# main.net
KiCad netlist of a schematic drawn in EAGLE
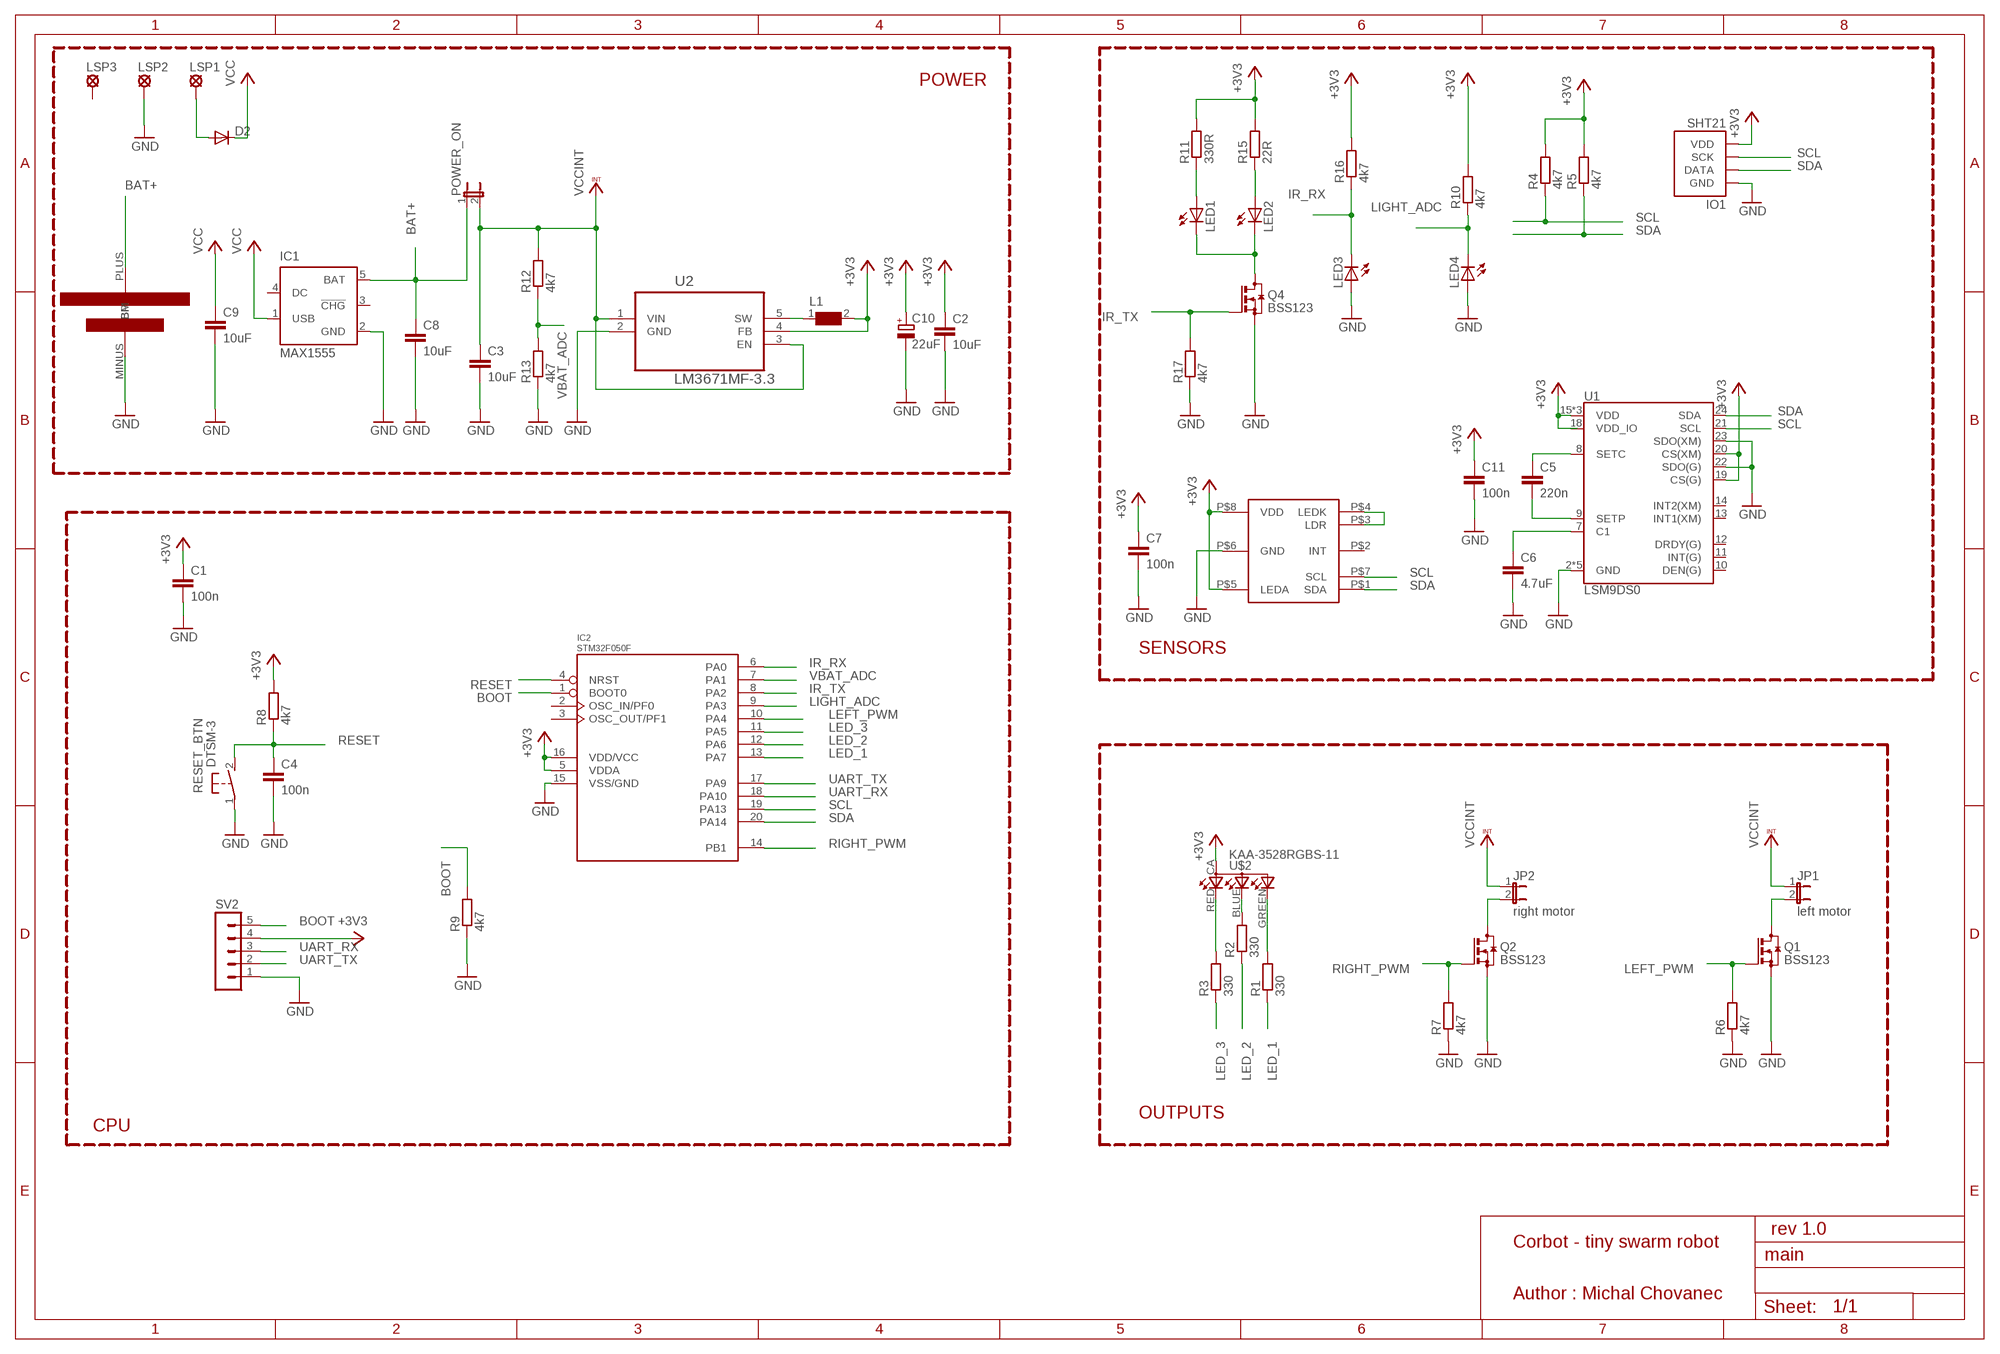
[diagram p0: schematic, sheet 1]

(export (version "E")
  (design (tool "Eeschema 10.0.6"))
  (components
    (comp (ref "C1")
      (value "100n")
      (footprint "eagle-import:C0805")
      (libsource (lib "eagle-import") (part "C-EUC0805"))
    )
    (comp (ref "C2")
      (value "10uF")
      (footprint "eagle-import:C0805")
      (libsource (lib "eagle-import") (part "C-EUC0805"))
    )
    (comp (ref "C3")
      (value "10uF")
      (footprint "eagle-import:C0805")
      (libsource (lib "eagle-import") (part "C-EUC0805"))
    )
    (comp (ref "C4")
      (value "100n")
      (footprint "eagle-import:C0805")
      (libsource (lib "eagle-import") (part "C-EUC0805"))
    )
    (comp (ref "C5")
      (value "220n")
      (footprint "eagle-import:C0805")
      (libsource (lib "eagle-import") (part "C-EUC0805"))
    )
    (comp (ref "C6")
      (value "4.7uF")
      (footprint "eagle-import:C0805")
      (libsource (lib "eagle-import") (part "C-EUC0805"))
    )
    (comp (ref "C7")
      (value "100n")
      (footprint "eagle-import:C0805")
      (libsource (lib "eagle-import") (part "C-EUC0805"))
    )
    (comp (ref "C8")
      (value "10uF")
      (footprint "eagle-import:C0805")
      (libsource (lib "eagle-import") (part "C-EUC0805"))
    )
    (comp (ref "C9")
      (value "10uF")
      (footprint "eagle-import:C0805")
      (libsource (lib "eagle-import") (part "C-EUC0805"))
    )
    (comp (ref "C10")
      (value "22uF")
      (footprint "eagle-import:153CLV-0505")
      (libsource (lib "eagle-import") (part "CPOL-EU153CLV-0505"))
    )
    (comp (ref "C11")
      (value "100n")
      (footprint "eagle-import:C0805")
      (libsource (lib "eagle-import") (part "C-EUC0805"))
    )
    (comp (ref "D2")
      (value "DIODE-DO-214AC")
      (footprint "eagle-import:DO-214AC")
      (libsource (lib "eagle-import") (part "DIODE-DO-214AC"))
    )
    (comp (ref "IC1")
      (value "MAX1555")
      (footprint "eagle-import:SOT23-5L")
      (fields (field (name "MF") "MAXIM") (field (name "MPN") "MAX1555EZK+T"))
      (libsource (lib "eagle-import") (part "MAX1555"))
    )
    (comp (ref "IC2")
      (value "STM32F050F")
      (footprint "eagle-import:TSSOP20")
      (libsource (lib "eagle-import") (part "STM32F050F"))
    )
    (comp (ref "IO1")
      (value "SHT21")
      (footprint "eagle-import:SHT2X")
      (libsource (lib "eagle-import") (part "SHT21"))
    )
    (comp (ref "JP1")
      (value "left motor")
      (footprint "eagle-import:JP1")
      (libsource (lib "eagle-import") (part "JP1E"))
    )
    (comp (ref "JP2")
      (value "right motor")
      (footprint "eagle-import:JP1")
      (libsource (lib "eagle-import") (part "JP1E"))
    )
    (comp (ref "L1")
      (value "WE-LQ-744032002_M")
      (footprint "eagle-import:WE-LQ_M")
      (fields (field (name "MPN") "744032002 "))
      (libsource (lib "eagle-import") (part "WE-LQ_M-744032002"))
    )
    (comp (ref "LED1")
      (value "LEDCHIPLED_1206")
      (footprint "eagle-import:CHIPLED_1206")
      (libsource (lib "eagle-import") (part "LEDCHIPLED_1206"))
    )
    (comp (ref "LED2")
      (value "LEDCHIPLED_1206")
      (footprint "eagle-import:CHIPLED_1206")
      (libsource (lib "eagle-import") (part "LEDCHIPLED_1206"))
    )
    (comp (ref "LED3")
      (value "LEDCHIPLED_1206")
      (footprint "eagle-import:CHIPLED_1206")
      (libsource (lib "eagle-import") (part "LEDCHIPLED_1206"))
    )
    (comp (ref "LED4")
      (value "LEDCHIPLED_1206")
      (footprint "eagle-import:CHIPLED_1206")
      (libsource (lib "eagle-import") (part "LEDCHIPLED_1206"))
    )
    (comp (ref "LSP1")
      (value "LSP13")
      (footprint "eagle-import:LSP13")
      (libsource (lib "eagle-import") (part "LSP13"))
    )
    (comp (ref "LSP2")
      (value "LSP13")
      (footprint "eagle-import:LSP13")
      (libsource (lib "eagle-import") (part "LSP13"))
    )
    (comp (ref "LSP3")
      (value "LSP13")
      (footprint "eagle-import:LSP13")
      (libsource (lib "eagle-import") (part "LSP13"))
    )
    (comp (ref "POWER_ON")
      (value "JP1E")
      (footprint "eagle-import:JP1")
      (libsource (lib "eagle-import") (part "JP1E"))
    )
    (comp (ref "Q1")
      (value "BSS123")
      (footprint "eagle-import:SOT23")
      (libsource (lib "eagle-import") (part "BSS123"))
    )
    (comp (ref "Q2")
      (value "BSS123")
      (footprint "eagle-import:SOT23")
      (libsource (lib "eagle-import") (part "BSS123"))
    )
    (comp (ref "Q4")
      (value "BSS123")
      (footprint "eagle-import:SOT23")
      (libsource (lib "eagle-import") (part "BSS123"))
    )
    (comp (ref "R1")
      (value "330")
      (footprint "eagle-import:M0805")
      (libsource (lib "eagle-import") (part "R-EU_M0805"))
    )
    (comp (ref "R2")
      (value "330")
      (footprint "eagle-import:M0805")
      (libsource (lib "eagle-import") (part "R-EU_M0805"))
    )
    (comp (ref "R3")
      (value "330")
      (footprint "eagle-import:M0805")
      (libsource (lib "eagle-import") (part "R-EU_M0805"))
    )
    (comp (ref "R4")
      (value "4k7")
      (footprint "eagle-import:M0805")
      (libsource (lib "eagle-import") (part "R-EU_M0805"))
    )
    (comp (ref "R5")
      (value "4k7")
      (footprint "eagle-import:M0805")
      (libsource (lib "eagle-import") (part "R-EU_M0805"))
    )
    (comp (ref "R6")
      (value "4k7")
      (footprint "eagle-import:M0805")
      (libsource (lib "eagle-import") (part "R-EU_M0805"))
    )
    (comp (ref "R7")
      (value "4k7")
      (footprint "eagle-import:M0805")
      (libsource (lib "eagle-import") (part "R-EU_M0805"))
    )
    (comp (ref "R8")
      (value "4k7")
      (footprint "eagle-import:M0805")
      (libsource (lib "eagle-import") (part "R-EU_M0805"))
    )
    (comp (ref "R9")
      (value "4k7")
      (footprint "eagle-import:M0805")
      (libsource (lib "eagle-import") (part "R-EU_M0805"))
    )
    (comp (ref "R10")
      (value "4k7")
      (footprint "eagle-import:M0805")
      (libsource (lib "eagle-import") (part "R-EU_M0805"))
    )
    (comp (ref "R11")
      (value "330R")
      (footprint "eagle-import:M0805")
      (libsource (lib "eagle-import") (part "R-EU_M0805"))
    )
    (comp (ref "R12")
      (value "4k7")
      (footprint "eagle-import:M0805")
      (libsource (lib "eagle-import") (part "R-EU_M0805"))
    )
    (comp (ref "R13")
      (value "4k7")
      (footprint "eagle-import:M0805")
      (libsource (lib "eagle-import") (part "R-EU_M0805"))
    )
    (comp (ref "R15")
      (value "22R")
      (footprint "eagle-import:M0805")
      (libsource (lib "eagle-import") (part "R-EU_M0805"))
    )
    (comp (ref "R16")
      (value "4k7")
      (footprint "eagle-import:M0805")
      (libsource (lib "eagle-import") (part "R-EU_M0805"))
    )
    (comp (ref "R17")
      (value "4k7")
      (footprint "eagle-import:M0805")
      (libsource (lib "eagle-import") (part "R-EU_M0805"))
    )
    (comp (ref "RESET_BTN")
      (value "DTSM-3")
      (footprint "eagle-import:DTSM-3")
      (libsource (lib "eagle-import") (part "DTSM-3"))
    )
    (comp (ref "SV2")
      (value "MA05-1")
      (footprint "eagle-import:MA05-1")
      (libsource (lib "eagle-import") (part "MA05-1"))
    )
    (comp (ref "U$1")
      (value "SMTU_2450N")
      (footprint "eagle-import:SMTU_2450N")
      (libsource (lib "eagle-import") (part "SMTU_2450N"))
    )
    (comp (ref "U$2")
      (value "KAA-3528RGBS-11")
      (footprint "eagle-import:LED-RGB")
      (libsource (lib "eagle-import") (part "KAA-3528RGBS-11"))
    )
    (comp (ref "U$3")
      (value "APDS9950")
      (footprint "eagle-import:APDS9950")
      (libsource (lib "eagle-import") (part "APDS9950"))
    )
    (comp (ref "U1")
      (value "LSM9DS0")
      (footprint "eagle-import:LGA-24")
      (libsource (lib "eagle-import") (part "LSM9DS0"))
    )
    (comp (ref "U2")
      (value "LM3671MF-3.3")
      (footprint "eagle-import:SOT95P284X122-5N")
      (libsource (lib "eagle-import") (part "LM3671MF-3.3"))
    )
  )
  (nets
    (net (code "1") (name "+3V3") (class "Default")
      (node (ref "C1") (pin "1") (pinfunction "1_1") (pintype "passive"))
      (node (ref "C10") (pin "+") (pinfunction "+_+") (pintype "passive"))
      (node (ref "C11") (pin "1") (pinfunction "1_1") (pintype "passive"))
      (node (ref "C2") (pin "1") (pinfunction "1_1") (pintype "passive"))
      (node (ref "C7") (pin "1") (pinfunction "1_1") (pintype "passive"))
      (node (ref "IC2") (pin "16") (pinfunction "VDD/VCC_16") (pintype "power_in"))
      (node (ref "IC2") (pin "5") (pinfunction "VDDA_5") (pintype "power_in"))
      (node (ref "IO1") (pin "5") (pinfunction "VDD_5") (pintype "power_in"))
      (node (ref "L1") (pin "2") (pinfunction "2_2") (pintype "passive"))
      (node (ref "R10") (pin "2") (pinfunction "2_2") (pintype "passive"))
      (node (ref "R11") (pin "2") (pinfunction "2_2") (pintype "passive"))
      (node (ref "R15") (pin "2") (pinfunction "2_2") (pintype "passive"))
      (node (ref "R16") (pin "2") (pinfunction "2_2") (pintype "passive"))
      (node (ref "R4") (pin "2") (pinfunction "2_2") (pintype "passive"))
      (node (ref "R5") (pin "2") (pinfunction "2_2") (pintype "passive"))
      (node (ref "R8") (pin "2") (pinfunction "2_2") (pintype "passive"))
      (node (ref "SV2") (pin "4") (pinfunction "4_4") (pintype "passive"))
      (node (ref "U$2") (pin "CA") (pinfunction "A_CA") (pintype "passive"))
      (node (ref "U$3") (pin "P$5") (pinfunction "LEDA_P$5") (pintype "bidirectional"))
      (node (ref "U$3") (pin "P$8") (pinfunction "VDD_P$8") (pintype "bidirectional"))
      (node (ref "U1") (pin "15") (pinfunction "VDD_15") (pintype "bidirectional"))
      (node (ref "U1") (pin "16") (pinfunction "VDD_16") (pintype "bidirectional"))
      (node (ref "U1") (pin "17") (pinfunction "VDD_17") (pintype "bidirectional"))
      (node (ref "U1") (pin "19") (pinfunction "CS(G)_19") (pintype "bidirectional"))
      (node (ref "U1") (pin "20") (pinfunction "CS(XM)_20") (pintype "bidirectional"))
      (node (ref "U2") (pin "4") (pinfunction "FB_4") (pintype "passive"))
    )
    (net (code "2") (name "/BAT+") (class "Default")
      (node (ref "C8") (pin "1") (pinfunction "1_1") (pintype "passive"))
      (node (ref "IC1") (pin "5") (pinfunction "BAT_5") (pintype "passive"))
      (node (ref "POWER_ON") (pin "1") (pinfunction "1_1") (pintype "passive"))
      (node (ref "U$1") (pin "PLUS") (pinfunction "BP_PLUS") (pintype "bidirectional"))
    )
    (net (code "3") (name "/BOOT") (class "Default")
      (node (ref "IC2") (pin "1") (pinfunction "BOOT0_1") (pintype "bidirectional"))
      (node (ref "R9") (pin "2") (pinfunction "2_2") (pintype "passive"))
      (node (ref "SV2") (pin "5") (pinfunction "5_5") (pintype "passive"))
    )
    (net (code "4") (name "/IR_RX") (class "Default")
      (node (ref "IC2") (pin "6") (pinfunction "PA0_6") (pintype "bidirectional"))
      (node (ref "LED3") (pin "C") (pinfunction "C_C") (pintype "passive"))
      (node (ref "R16") (pin "1") (pinfunction "1_1") (pintype "passive"))
    )
    (net (code "5") (name "/IR_TX") (class "Default")
      (node (ref "IC2") (pin "8") (pinfunction "PA2_8") (pintype "bidirectional"))
      (node (ref "Q4") (pin "1") (pinfunction "G_1") (pintype "passive"))
      (node (ref "R17") (pin "2") (pinfunction "2_2") (pintype "passive"))
    )
    (net (code "6") (name "/LED_1") (class "Default")
      (node (ref "IC2") (pin "13") (pinfunction "PA7_13") (pintype "bidirectional"))
      (node (ref "R1") (pin "1") (pinfunction "1_1") (pintype "passive"))
    )
    (net (code "7") (name "/LED_2") (class "Default")
      (node (ref "IC2") (pin "12") (pinfunction "PA6_12") (pintype "bidirectional"))
      (node (ref "R2") (pin "1") (pinfunction "1_1") (pintype "passive"))
    )
    (net (code "8") (name "/LED_3") (class "Default")
      (node (ref "IC2") (pin "11") (pinfunction "PA5_11") (pintype "bidirectional"))
      (node (ref "R3") (pin "1") (pinfunction "1_1") (pintype "passive"))
    )
    (net (code "9") (name "/LEFT_PWM") (class "Default")
      (node (ref "IC2") (pin "10") (pinfunction "PA4_10") (pintype "bidirectional"))
      (node (ref "Q1") (pin "1") (pinfunction "G_1") (pintype "passive"))
      (node (ref "R6") (pin "2") (pinfunction "2_2") (pintype "passive"))
    )
    (net (code "10") (name "/LIGHT_ADC") (class "Default")
      (node (ref "IC2") (pin "9") (pinfunction "PA3_9") (pintype "bidirectional"))
      (node (ref "LED4") (pin "C") (pinfunction "C_C") (pintype "passive"))
      (node (ref "R10") (pin "1") (pinfunction "1_1") (pintype "passive"))
    )
    (net (code "11") (name "/RESET") (class "Default")
      (node (ref "C4") (pin "1") (pinfunction "1_1") (pintype "passive"))
      (node (ref "IC2") (pin "4") (pinfunction "NRST_4") (pintype "bidirectional"))
      (node (ref "R8") (pin "1") (pinfunction "1_1") (pintype "passive"))
      (node (ref "RESET_BTN") (pin "2") (pinfunction "2_2") (pintype "passive"))
    )
    (net (code "12") (name "/RIGHT_PWM") (class "Default")
      (node (ref "IC2") (pin "14") (pinfunction "PB1_14") (pintype "bidirectional"))
      (node (ref "Q2") (pin "1") (pinfunction "G_1") (pintype "passive"))
      (node (ref "R7") (pin "2") (pinfunction "2_2") (pintype "passive"))
    )
    (net (code "13") (name "/SCL") (class "Default")
      (node (ref "IC2") (pin "19") (pinfunction "PA13_19") (pintype "bidirectional"))
      (node (ref "IO1") (pin "4") (pinfunction "SCK_4") (pintype "input"))
      (node (ref "R4") (pin "1") (pinfunction "1_1") (pintype "passive"))
      (node (ref "U$3") (pin "P$7") (pinfunction "SCL_P$7") (pintype "bidirectional"))
      (node (ref "U1") (pin "21") (pinfunction "SCL_21") (pintype "bidirectional"))
    )
    (net (code "14") (name "/SDA") (class "Default")
      (node (ref "IC2") (pin "20") (pinfunction "PA14_20") (pintype "bidirectional"))
      (node (ref "IO1") (pin "1") (pinfunction "DATA_1") (pintype "bidirectional"))
      (node (ref "R5") (pin "1") (pinfunction "1_1") (pintype "passive"))
      (node (ref "U$3") (pin "P$1") (pinfunction "SDA_P$1") (pintype "bidirectional"))
      (node (ref "U1") (pin "24") (pinfunction "SDA_24") (pintype "bidirectional"))
    )
    (net (code "15") (name "/UART_RX") (class "Default")
      (node (ref "IC2") (pin "18") (pinfunction "PA10_18") (pintype "bidirectional"))
      (node (ref "SV2") (pin "3") (pinfunction "3_3") (pintype "passive"))
    )
    (net (code "16") (name "/UART_TX") (class "Default")
      (node (ref "IC2") (pin "17") (pinfunction "PA9_17") (pintype "bidirectional"))
      (node (ref "SV2") (pin "2") (pinfunction "2_2") (pintype "passive"))
    )
    (net (code "17") (name "/VBAT_ADC") (class "Default")
      (node (ref "IC2") (pin "7") (pinfunction "PA1_7") (pintype "bidirectional"))
      (node (ref "R12") (pin "1") (pinfunction "1_1") (pintype "passive"))
      (node (ref "R13") (pin "2") (pinfunction "2_2") (pintype "passive"))
    )
    (net (code "18") (name "GND") (class "Default")
      (node (ref "C1") (pin "2") (pinfunction "2_2") (pintype "passive"))
      (node (ref "C10") (pin "-") (pinfunction "-_-") (pintype "passive"))
      (node (ref "C11") (pin "2") (pinfunction "2_2") (pintype "passive"))
      (node (ref "C2") (pin "2") (pinfunction "2_2") (pintype "passive"))
      (node (ref "C3") (pin "2") (pinfunction "2_2") (pintype "passive"))
      (node (ref "C4") (pin "2") (pinfunction "2_2") (pintype "passive"))
      (node (ref "C6") (pin "2") (pinfunction "2_2") (pintype "passive"))
      (node (ref "C7") (pin "2") (pinfunction "2_2") (pintype "passive"))
      (node (ref "C8") (pin "2") (pinfunction "2_2") (pintype "passive"))
      (node (ref "C9") (pin "2") (pinfunction "2_2") (pintype "passive"))
      (node (ref "IC1") (pin "2") (pinfunction "GND_2") (pintype "power_in"))
      (node (ref "IC2") (pin "15") (pinfunction "VSS/GND_15") (pintype "power_in"))
      (node (ref "IO1") (pin "2") (pinfunction "GND_2") (pintype "power_in"))
      (node (ref "LED3") (pin "A") (pinfunction "A_A") (pintype "passive"))
      (node (ref "LED4") (pin "A") (pinfunction "A_A") (pintype "passive"))
      (node (ref "LSP2") (pin "MP") (pinfunction "MP_MP") (pintype "passive"))
      (node (ref "Q1") (pin "2") (pinfunction "S_2") (pintype "passive"))
      (node (ref "Q2") (pin "2") (pinfunction "S_2") (pintype "passive"))
      (node (ref "Q4") (pin "2") (pinfunction "S_2") (pintype "passive"))
      (node (ref "R13") (pin "1") (pinfunction "1_1") (pintype "passive"))
      (node (ref "R17") (pin "1") (pinfunction "1_1") (pintype "passive"))
      (node (ref "R6") (pin "1") (pinfunction "1_1") (pintype "passive"))
      (node (ref "R7") (pin "1") (pinfunction "1_1") (pintype "passive"))
      (node (ref "R9") (pin "1") (pinfunction "1_1") (pintype "passive"))
      (node (ref "RESET_BTN") (pin "1") (pinfunction "1_1") (pintype "passive"))
      (node (ref "SV2") (pin "1") (pinfunction "1_1") (pintype "passive"))
      (node (ref "U$1") (pin "MINUS") (pinfunction "BM_MINUS") (pintype "bidirectional"))
      (node (ref "U$3") (pin "P$6") (pinfunction "GND_P$6") (pintype "bidirectional"))
      (node (ref "U1") (pin "2") (pinfunction "GND_2") (pintype "bidirectional"))
      (node (ref "U1") (pin "22") (pinfunction "SDO(G)_22") (pintype "bidirectional"))
      (node (ref "U1") (pin "23") (pinfunction "SDO(XM)_23") (pintype "bidirectional"))
      (node (ref "U1") (pin "3") (pinfunction "GND_3") (pintype "bidirectional"))
      (node (ref "U1") (pin "4") (pinfunction "GND_4") (pintype "bidirectional"))
      (node (ref "U1") (pin "5") (pinfunction "GND_5") (pintype "bidirectional"))
      (node (ref "U1") (pin "6") (pinfunction "GND_6") (pintype "bidirectional"))
      (node (ref "U2") (pin "2") (pinfunction "GND_2") (pintype "passive"))
    )
    (net (code "19") (name "Net-(D2-PadA)") (class "Default")
      (node (ref "D2") (pin "A") (pinfunction "A_A") (pintype "passive"))
      (node (ref "LSP1") (pin "MP") (pinfunction "MP_MP") (pintype "passive"))
    )
    (net (code "20") (name "Net-(LED1-PadA)") (class "Default")
      (node (ref "LED1") (pin "A") (pinfunction "A_A") (pintype "passive"))
      (node (ref "R11") (pin "1") (pinfunction "1_1") (pintype "passive"))
    )
    (net (code "21") (name "Net-(LED2-PadA)") (class "Default")
      (node (ref "LED2") (pin "A") (pinfunction "A_A") (pintype "passive"))
      (node (ref "R15") (pin "1") (pinfunction "1_1") (pintype "passive"))
    )
    (net (code "22") (name "Net-(Q1-D)") (class "Default")
      (node (ref "JP1") (pin "2") (pinfunction "2_2") (pintype "passive"))
      (node (ref "Q1") (pin "3") (pinfunction "D_3") (pintype "passive"))
    )
    (net (code "23") (name "Net-(Q2-D)") (class "Default")
      (node (ref "JP2") (pin "2") (pinfunction "2_2") (pintype "passive"))
      (node (ref "Q2") (pin "3") (pinfunction "D_3") (pintype "passive"))
    )
    (net (code "24") (name "Net-(Q4-D)") (class "Default")
      (node (ref "LED1") (pin "C") (pinfunction "C_C") (pintype "passive"))
      (node (ref "LED2") (pin "C") (pinfunction "C_C") (pintype "passive"))
      (node (ref "Q4") (pin "3") (pinfunction "D_3") (pintype "passive"))
    )
    (net (code "25") (name "Net-(U$2-CBLUE)") (class "Default")
      (node (ref "R2") (pin "2") (pinfunction "2_2") (pintype "passive"))
      (node (ref "U$2") (pin "BLUE") (pinfunction "CBLUE_BLUE") (pintype "passive"))
    )
    (net (code "26") (name "Net-(U$2-CGREEN)") (class "Default")
      (node (ref "R1") (pin "2") (pinfunction "2_2") (pintype "passive"))
      (node (ref "U$2") (pin "GREEN") (pinfunction "CGREEN_GREEN") (pintype "passive"))
    )
    (net (code "27") (name "Net-(U$2-CRED)") (class "Default")
      (node (ref "R3") (pin "2") (pinfunction "2_2") (pintype "passive"))
      (node (ref "U$2") (pin "RED") (pinfunction "CRED_RED") (pintype "passive"))
    )
    (net (code "28") (name "Net-(U$3-LDR)") (class "Default")
      (node (ref "U$3") (pin "P$3") (pinfunction "LDR_P$3") (pintype "bidirectional"))
      (node (ref "U$3") (pin "P$4") (pinfunction "LEDK_P$4") (pintype "bidirectional"))
    )
    (net (code "29") (name "Net-(U1-C1)") (class "Default")
      (node (ref "C6") (pin "1") (pinfunction "1_1") (pintype "passive"))
      (node (ref "U1") (pin "7") (pinfunction "C1_7") (pintype "bidirectional"))
    )
    (net (code "30") (name "Net-(U1-SETC)") (class "Default")
      (node (ref "C5") (pin "1") (pinfunction "1_1") (pintype "passive"))
      (node (ref "U1") (pin "8") (pinfunction "SETC_8") (pintype "bidirectional"))
    )
    (net (code "31") (name "Net-(U1-SETP)") (class "Default")
      (node (ref "C5") (pin "2") (pinfunction "2_2") (pintype "passive"))
      (node (ref "U1") (pin "9") (pinfunction "SETP_9") (pintype "bidirectional"))
    )
    (net (code "32") (name "Net-(U2-SW)") (class "Default")
      (node (ref "L1") (pin "1") (pinfunction "1_1") (pintype "passive"))
      (node (ref "U2") (pin "5") (pinfunction "SW_5") (pintype "output"))
    )
    (net (code "33") (name "VCC") (class "Default")
      (node (ref "C9") (pin "1") (pinfunction "1_1") (pintype "passive"))
      (node (ref "D2") (pin "C") (pinfunction "C_C") (pintype "passive"))
      (node (ref "IC1") (pin "1") (pinfunction "USB_1") (pintype "input"))
    )
    (net (code "34") (name "VCCINT") (class "Default")
      (node (ref "C3") (pin "1") (pinfunction "1_1") (pintype "passive"))
      (node (ref "JP1") (pin "1") (pinfunction "1_1") (pintype "passive"))
      (node (ref "JP2") (pin "1") (pinfunction "1_1") (pintype "passive"))
      (node (ref "POWER_ON") (pin "2") (pinfunction "2_2") (pintype "passive"))
      (node (ref "R12") (pin "2") (pinfunction "2_2") (pintype "passive"))
      (node (ref "U2") (pin "1") (pinfunction "VIN_1") (pintype "input"))
      (node (ref "U2") (pin "3") (pinfunction "EN_3") (pintype "passive"))
    )
    (net (code "35") (name "unconnected-(IC1-DC-Pad4)") (class "Default")
      (node (ref "IC1") (pin "4") (pinfunction "DC_4") (pintype "input"))
    )
    (net (code "36") (name "unconnected-(IC1-~{CHG}-Pad3)") (class "Default")
      (node (ref "IC1") (pin "3") (pinfunction "~{CHG}_3") (pintype "output"))
    )
    (net (code "37") (name "unconnected-(IC2-OSC_IN{slash}PF0-Pad2)") (class "Default")
      (node (ref "IC2") (pin "2") (pinfunction "OSC_IN/PF0_2") (pintype "bidirectional"))
    )
    (net (code "38") (name "unconnected-(IC2-OSC_OUT{slash}PF1-Pad3)") (class "Default")
      (node (ref "IC2") (pin "3") (pinfunction "OSC_OUT/PF1_3") (pintype "bidirectional"))
    )
    (net (code "39") (name "unconnected-(LSP3-PadMP)") (class "Default")
      (node (ref "LSP3") (pin "MP") (pinfunction "MP_MP") (pintype "passive"))
    )
    (net (code "40") (name "unconnected-(U$3-INT-PadP$2)") (class "Default")
      (node (ref "U$3") (pin "P$2") (pinfunction "INT_P$2") (pintype "bidirectional"))
    )
    (net (code "41") (name "unconnected-(U1-DEN(G)-Pad10)") (class "Default")
      (node (ref "U1") (pin "10") (pinfunction "DEN(G)_10") (pintype "bidirectional"))
    )
    (net (code "42") (name "unconnected-(U1-DRDY(G)-Pad12)") (class "Default")
      (node (ref "U1") (pin "12") (pinfunction "DRDY(G)_12") (pintype "bidirectional"))
    )
    (net (code "43") (name "unconnected-(U1-INT(G)-Pad11)") (class "Default")
      (node (ref "U1") (pin "11") (pinfunction "INT(G)_11") (pintype "bidirectional"))
    )
    (net (code "44") (name "unconnected-(U1-INT1(XM)-Pad13)") (class "Default")
      (node (ref "U1") (pin "13") (pinfunction "INT1(XM)_13") (pintype "bidirectional"))
    )
    (net (code "45") (name "unconnected-(U1-INT2(XM)-Pad14)") (class "Default")
      (node (ref "U1") (pin "14") (pinfunction "INT2(XM)_14") (pintype "bidirectional"))
    )
    (net (code "46") (name "unconnected-(U1-VDD_IO-Pad18)") (class "Default")
      (node (ref "U1") (pin "18") (pinfunction "VDD_IO_18") (pintype "bidirectional"))
    )
  )
)
